# FIANO.net
KiCad netlist of a schematic drawn in EasyEDA Pro
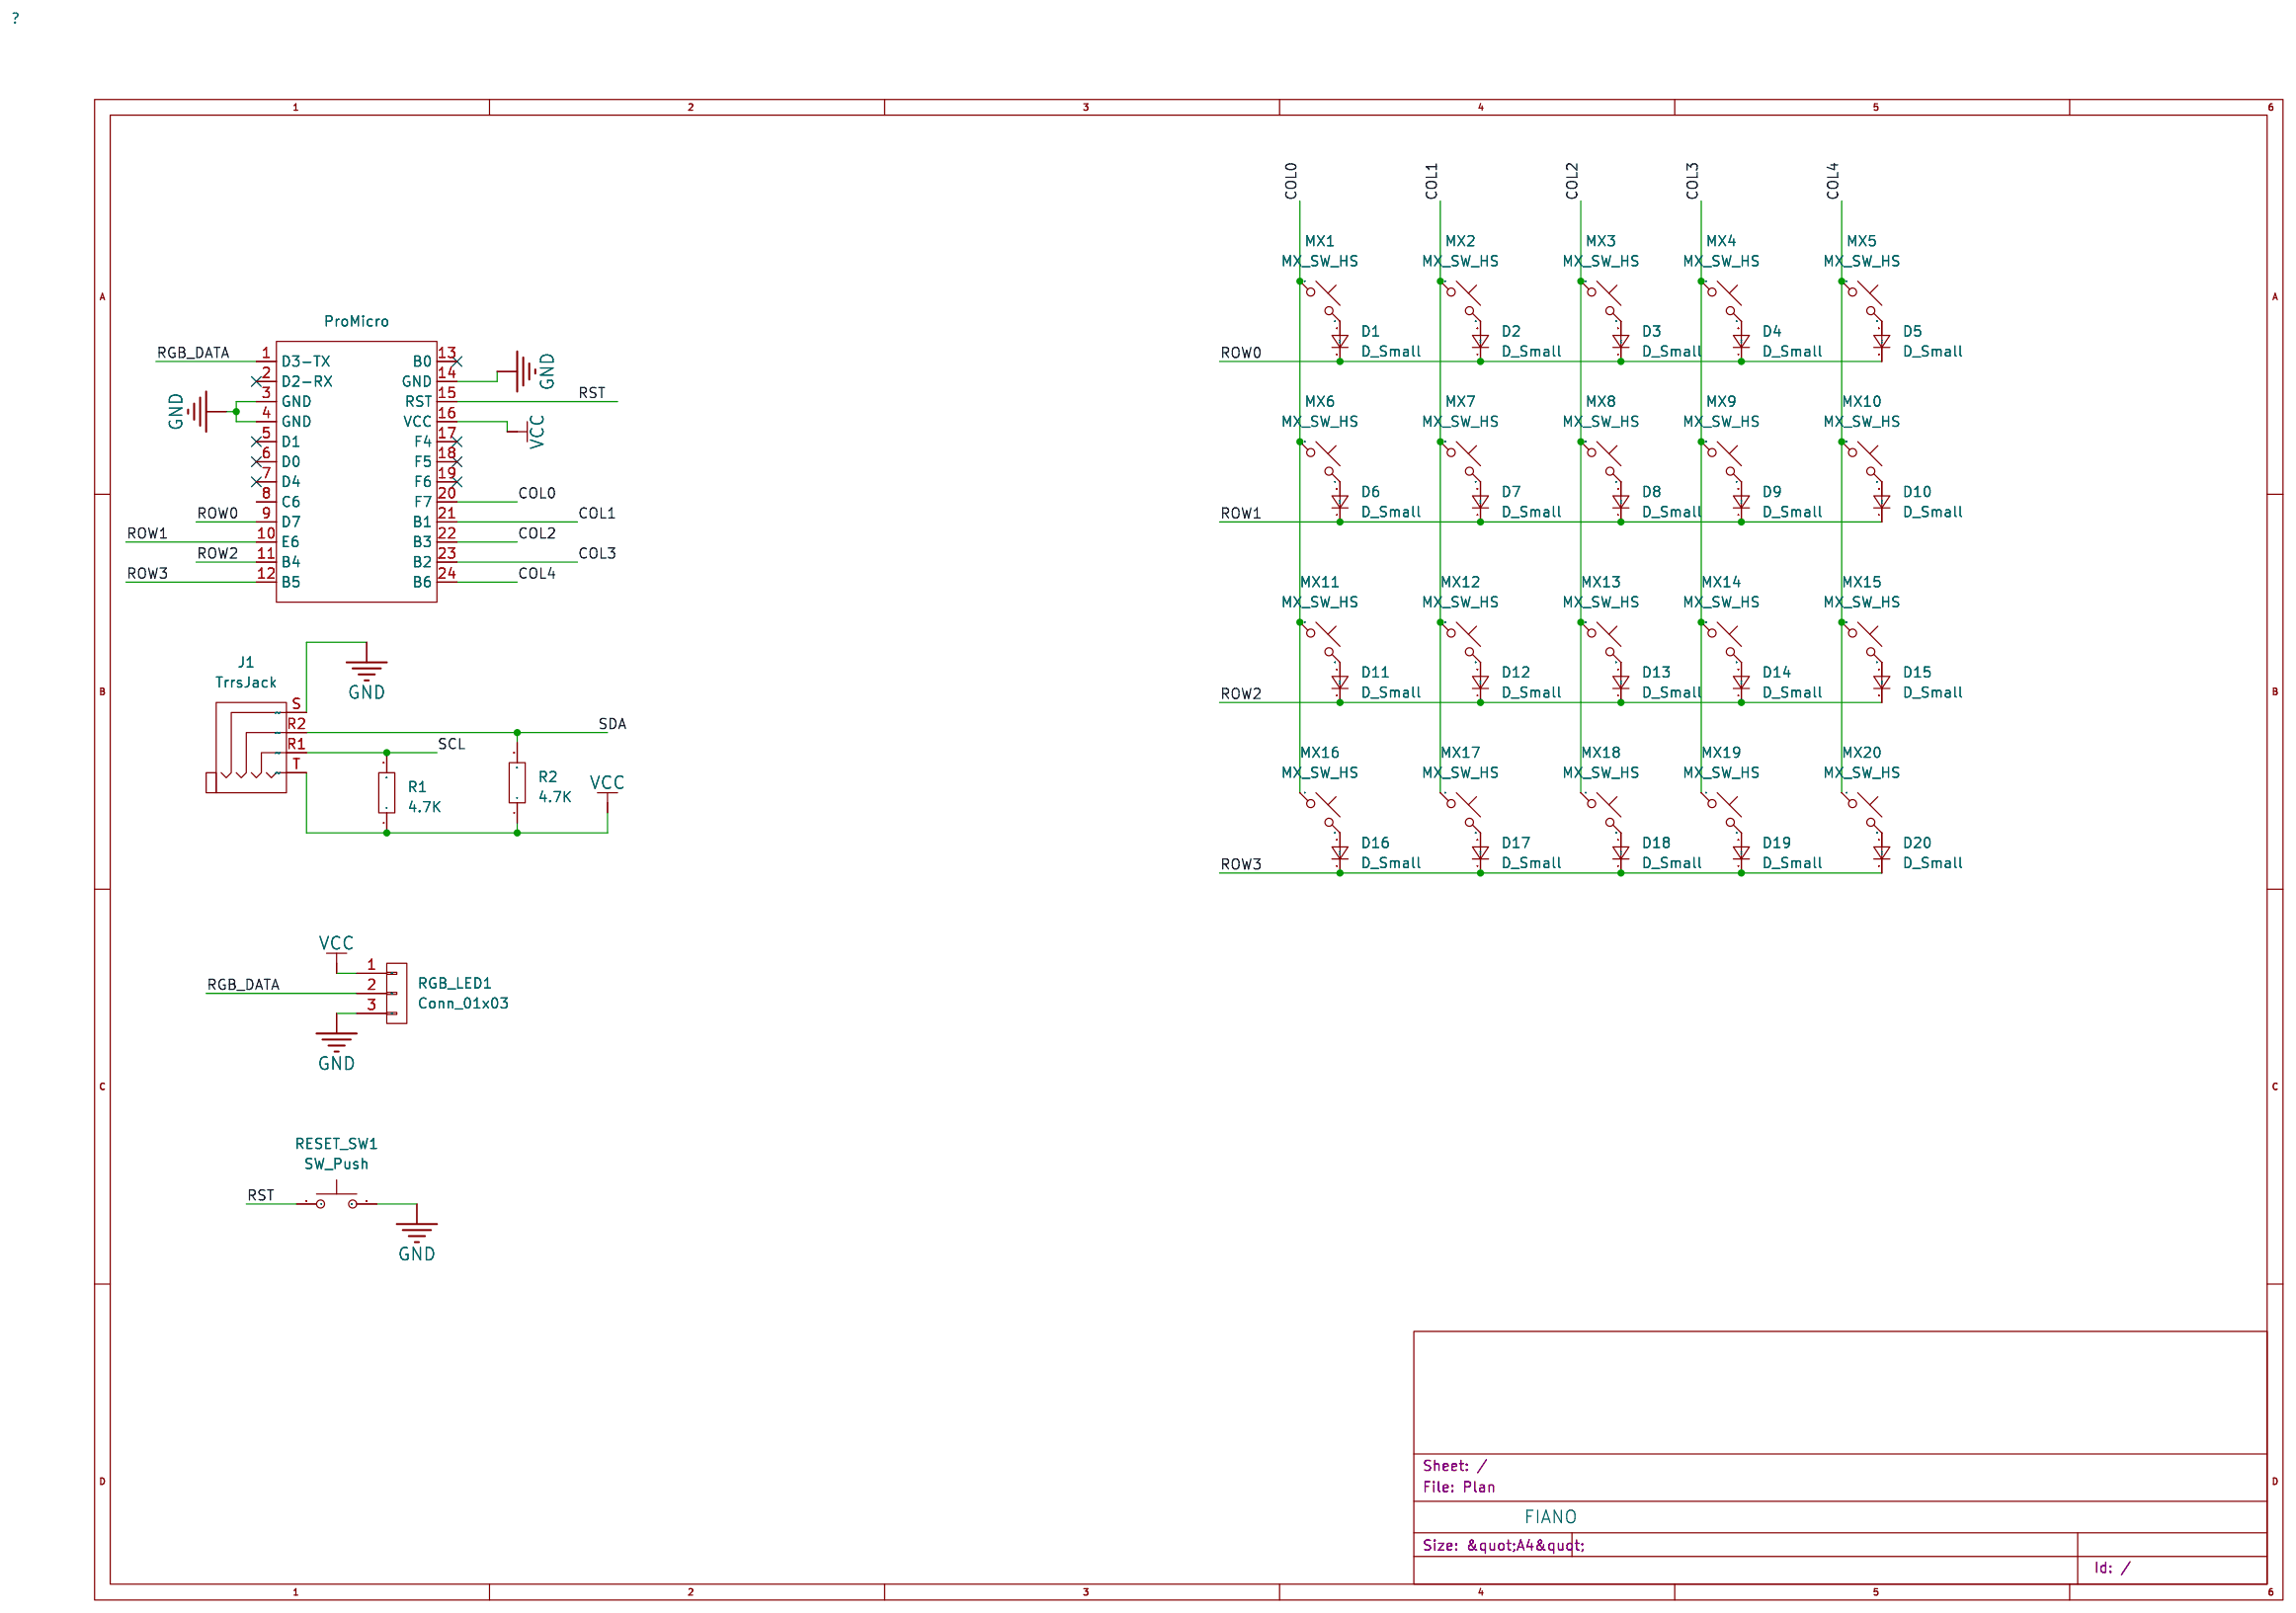
[diagram p0: schematic sheet]

(export (version "E")
  (design (tool "Eeschema 10.0.6"))
  (components
    (comp (ref "D1")
      (value "D_Small")
      (footprint "easyedapro:Keebio-Parts.pretty-master:Diode-hybrid-3pad")
      (description "Diode, small symbol")
      (libsource (lib "easyedapro") (part "Device_D_Small"))
    )
    (comp (ref "D2")
      (value "D_Small")
      (footprint "easyedapro:Keebio-Parts.pretty-master:Diode-hybrid-3pad")
      (description "Diode, small symbol")
      (libsource (lib "easyedapro") (part "Device_D_Small"))
    )
    (comp (ref "D3")
      (value "D_Small")
      (footprint "easyedapro:Keebio-Parts.pretty-master:Diode-hybrid-3pad")
      (description "Diode, small symbol")
      (libsource (lib "easyedapro") (part "Device_D_Small"))
    )
    (comp (ref "D4")
      (value "D_Small")
      (footprint "easyedapro:Keebio-Parts.pretty-master:Diode-hybrid-3pad")
      (description "Diode, small symbol")
      (libsource (lib "easyedapro") (part "Device_D_Small"))
    )
    (comp (ref "D5")
      (value "D_Small")
      (footprint "easyedapro:Keebio-Parts.pretty-master:Diode-hybrid-3pad")
      (description "Diode, small symbol")
      (libsource (lib "easyedapro") (part "Device_D_Small"))
    )
    (comp (ref "D6")
      (value "D_Small")
      (footprint "easyedapro:Keebio-Parts.pretty-master:Diode-hybrid-3pad")
      (description "Diode, small symbol")
      (libsource (lib "easyedapro") (part "Device_D_Small"))
    )
    (comp (ref "D7")
      (value "D_Small")
      (footprint "easyedapro:Keebio-Parts.pretty-master:Diode-hybrid-3pad")
      (description "Diode, small symbol")
      (libsource (lib "easyedapro") (part "Device_D_Small"))
    )
    (comp (ref "D8")
      (value "D_Small")
      (footprint "easyedapro:Keebio-Parts.pretty-master:Diode-hybrid-3pad")
      (description "Diode, small symbol")
      (libsource (lib "easyedapro") (part "Device_D_Small"))
    )
    (comp (ref "D9")
      (value "D_Small")
      (footprint "easyedapro:Keebio-Parts.pretty-master:Diode-hybrid-3pad")
      (description "Diode, small symbol")
      (libsource (lib "easyedapro") (part "Device_D_Small"))
    )
    (comp (ref "D10")
      (value "D_Small")
      (footprint "easyedapro:Keebio-Parts.pretty-master:Diode-hybrid-3pad")
      (description "Diode, small symbol")
      (libsource (lib "easyedapro") (part "Device_D_Small"))
    )
    (comp (ref "D11")
      (value "D_Small")
      (footprint "easyedapro:Keebio-Parts.pretty-master:Diode-hybrid-3pad")
      (description "Diode, small symbol")
      (libsource (lib "easyedapro") (part "Device_D_Small"))
    )
    (comp (ref "D12")
      (value "D_Small")
      (footprint "easyedapro:Keebio-Parts.pretty-master:Diode-hybrid-3pad")
      (description "Diode, small symbol")
      (libsource (lib "easyedapro") (part "Device_D_Small"))
    )
    (comp (ref "D13")
      (value "D_Small")
      (footprint "easyedapro:Keebio-Parts.pretty-master:Diode-hybrid-3pad")
      (description "Diode, small symbol")
      (libsource (lib "easyedapro") (part "Device_D_Small"))
    )
    (comp (ref "D14")
      (value "D_Small")
      (footprint "easyedapro:Keebio-Parts.pretty-master:Diode-hybrid-3pad")
      (description "Diode, small symbol")
      (libsource (lib "easyedapro") (part "Device_D_Small"))
    )
    (comp (ref "D15")
      (value "D_Small")
      (footprint "easyedapro:Keebio-Parts.pretty-master:Diode-hybrid-3pad")
      (description "Diode, small symbol")
      (libsource (lib "easyedapro") (part "Device_D_Small"))
    )
    (comp (ref "D16")
      (value "D_Small")
      (footprint "easyedapro:Keebio-Parts.pretty-master:Diode-hybrid-3pad")
      (description "Diode, small symbol")
      (libsource (lib "easyedapro") (part "Device_D_Small"))
    )
    (comp (ref "D17")
      (value "D_Small")
      (footprint "easyedapro:Keebio-Parts.pretty-master:Diode-hybrid-3pad")
      (description "Diode, small symbol")
      (libsource (lib "easyedapro") (part "Device_D_Small"))
    )
    (comp (ref "D18")
      (value "D_Small")
      (footprint "easyedapro:Keebio-Parts.pretty-master:Diode-hybrid-3pad")
      (description "Diode, small symbol")
      (libsource (lib "easyedapro") (part "Device_D_Small"))
    )
    (comp (ref "D19")
      (value "D_Small")
      (footprint "easyedapro:Keebio-Parts.pretty-master:Diode-hybrid-3pad")
      (description "Diode, small symbol")
      (libsource (lib "easyedapro") (part "Device_D_Small"))
    )
    (comp (ref "D20")
      (value "D_Small")
      (footprint "easyedapro:Keebio-Parts.pretty-master:Diode-hybrid-3pad")
      (description "Diode, small symbol")
      (libsource (lib "easyedapro") (part "Device_D_Small"))
    )
    (comp (ref "J1")
      (value "TrrsJack")
      (footprint "easyedapro:PCM_marbastlib-xp-various:CON_MJ-4PP-9")
      (description "Audio Jack, 4 Poles (TRRS)")
      (libsource (lib "easyedapro") (part "Connector_Audio_AudioJack4"))
    )
    (comp (ref "MX1")
      (value "MX_SW_HS")
      (footprint "easyedapro:PCM_marbastlib-mx:SW_MX_1u")
      (libsource (lib "easyedapro") (part "PCM_marbastlib-mx_MX_SW_HS_CPG151101S11"))
    )
    (comp (ref "MX2")
      (value "MX_SW_HS")
      (footprint "easyedapro:PCM_marbastlib-mx:SW_MX_1u")
      (libsource (lib "easyedapro") (part "PCM_marbastlib-mx_MX_SW_HS_CPG151101S11"))
    )
    (comp (ref "MX3")
      (value "MX_SW_HS")
      (footprint "easyedapro:PCM_marbastlib-mx:SW_MX_1u")
      (libsource (lib "easyedapro") (part "PCM_marbastlib-mx_MX_SW_HS_CPG151101S11"))
    )
    (comp (ref "MX4")
      (value "MX_SW_HS")
      (footprint "easyedapro:PCM_marbastlib-mx:SW_MX_1u")
      (libsource (lib "easyedapro") (part "PCM_marbastlib-mx_MX_SW_HS_CPG151101S11"))
    )
    (comp (ref "MX5")
      (value "MX_SW_HS")
      (footprint "easyedapro:PCM_marbastlib-mx:SW_MX_1u")
      (libsource (lib "easyedapro") (part "PCM_marbastlib-mx_MX_SW_HS_CPG151101S11"))
    )
    (comp (ref "MX6")
      (value "MX_SW_HS")
      (footprint "easyedapro:PCM_marbastlib-mx:SW_MX_1u")
      (libsource (lib "easyedapro") (part "PCM_marbastlib-mx_MX_SW_HS_CPG151101S11"))
    )
    (comp (ref "MX7")
      (value "MX_SW_HS")
      (footprint "easyedapro:PCM_marbastlib-mx:SW_MX_1u")
      (libsource (lib "easyedapro") (part "PCM_marbastlib-mx_MX_SW_HS_CPG151101S11"))
    )
    (comp (ref "MX8")
      (value "MX_SW_HS")
      (footprint "easyedapro:PCM_marbastlib-mx:SW_MX_1u")
      (libsource (lib "easyedapro") (part "PCM_marbastlib-mx_MX_SW_HS_CPG151101S11"))
    )
    (comp (ref "MX9")
      (value "MX_SW_HS")
      (footprint "easyedapro:PCM_marbastlib-mx:SW_MX_1u")
      (libsource (lib "easyedapro") (part "PCM_marbastlib-mx_MX_SW_HS_CPG151101S11"))
    )
    (comp (ref "MX10")
      (value "MX_SW_HS")
      (footprint "easyedapro:PCM_marbastlib-mx:SW_MX_1u")
      (libsource (lib "easyedapro") (part "PCM_marbastlib-mx_MX_SW_HS_CPG151101S11"))
    )
    (comp (ref "MX11")
      (value "MX_SW_HS")
      (footprint "easyedapro:PCM_marbastlib-mx:SW_MX_1u")
      (libsource (lib "easyedapro") (part "PCM_marbastlib-mx_MX_SW_HS_CPG151101S11"))
    )
    (comp (ref "MX12")
      (value "MX_SW_HS")
      (footprint "easyedapro:PCM_marbastlib-mx:SW_MX_1u")
      (libsource (lib "easyedapro") (part "PCM_marbastlib-mx_MX_SW_HS_CPG151101S11"))
    )
    (comp (ref "MX13")
      (value "MX_SW_HS")
      (footprint "easyedapro:PCM_marbastlib-mx:SW_MX_1u")
      (libsource (lib "easyedapro") (part "PCM_marbastlib-mx_MX_SW_HS_CPG151101S11"))
    )
    (comp (ref "MX14")
      (value "MX_SW_HS")
      (footprint "easyedapro:PCM_marbastlib-mx:SW_MX_1u")
      (libsource (lib "easyedapro") (part "PCM_marbastlib-mx_MX_SW_HS_CPG151101S11"))
    )
    (comp (ref "MX15")
      (value "MX_SW_HS")
      (footprint "easyedapro:PCM_marbastlib-mx:SW_MX_1u")
      (libsource (lib "easyedapro") (part "PCM_marbastlib-mx_MX_SW_HS_CPG151101S11"))
    )
    (comp (ref "MX16")
      (value "MX_SW_HS")
      (footprint "easyedapro:PCM_marbastlib-mx:SW_MX_1u")
      (libsource (lib "easyedapro") (part "PCM_marbastlib-mx_MX_SW_HS_CPG151101S11"))
    )
    (comp (ref "MX17")
      (value "MX_SW_HS")
      (footprint "easyedapro:PCM_marbastlib-mx:SW_MX_1u")
      (libsource (lib "easyedapro") (part "PCM_marbastlib-mx_MX_SW_HS_CPG151101S11"))
    )
    (comp (ref "MX18")
      (value "MX_SW_HS")
      (footprint "easyedapro:PCM_marbastlib-mx:SW_MX_1u")
      (libsource (lib "easyedapro") (part "PCM_marbastlib-mx_MX_SW_HS_CPG151101S11"))
    )
    (comp (ref "MX19")
      (value "MX_SW_HS")
      (footprint "easyedapro:PCM_marbastlib-mx:SW_MX_1u")
      (libsource (lib "easyedapro") (part "PCM_marbastlib-mx_MX_SW_HS_CPG151101S11"))
    )
    (comp (ref "MX20")
      (value "MX_SW_HS")
      (footprint "easyedapro:PCM_marbastlib-mx:SW_MX_1u")
      (libsource (lib "easyedapro") (part "PCM_marbastlib-mx_MX_SW_HS_CPG151101S11"))
    )
    (comp (ref "R1")
      (value "4.7K")
      (footprint "easyedapro:R0603")
      (libsource (lib "easyedapro") (part "Res"))
    )
    (comp (ref "R2")
      (value "4.7K")
      (footprint "easyedapro:R0603")
      (libsource (lib "easyedapro") (part "Res"))
    )
    (comp (ref "RESET_SW1")
      (value "SW_Push")
      (description "Push button switch, generic, two pins")
      (libsource (lib "easyedapro") (part "Switch_SW_Push"))
    )
    (comp (ref "RGB_LED1")
      (value "Conn_01x03")
      (libsource (lib "easyedapro") (part "Connector_Generic_Conn_01x03"))
    )
    (comp (ref "U1")
      (value "ProMicro")
      (footprint "easyedapro:PCM_marbastlib-xp-promicroish:ProMicro_USBup")
      (description "Symbol for an Arduino Pro Micro")
      (libsource (lib "easyedapro") (part "PCM_marbastlib-promicroish_Arduino_ProMicro"))
    )
  )
  (nets
    (net (code "1") (name "/COL0") (class "Default")
      (node (ref "MX1") (pin "1") (pinfunction "1_1") (pintype "unspecified"))
      (node (ref "MX11") (pin "1") (pinfunction "1_1") (pintype "unspecified"))
      (node (ref "MX16") (pin "1") (pinfunction "1_1") (pintype "unspecified"))
      (node (ref "MX6") (pin "1") (pinfunction "1_1") (pintype "unspecified"))
      (node (ref "U1") (pin "20") (pinfunction "F7_20") (pintype "bidirectional"))
    )
    (net (code "2") (name "/COL1") (class "Default")
      (node (ref "MX12") (pin "1") (pinfunction "1_1") (pintype "unspecified"))
      (node (ref "MX17") (pin "1") (pinfunction "1_1") (pintype "unspecified"))
      (node (ref "MX2") (pin "1") (pinfunction "1_1") (pintype "unspecified"))
      (node (ref "MX7") (pin "1") (pinfunction "1_1") (pintype "unspecified"))
      (node (ref "U1") (pin "21") (pinfunction "B1_21") (pintype "bidirectional"))
    )
    (net (code "3") (name "/COL2") (class "Default")
      (node (ref "MX13") (pin "1") (pinfunction "1_1") (pintype "unspecified"))
      (node (ref "MX18") (pin "1") (pinfunction "1_1") (pintype "unspecified"))
      (node (ref "MX3") (pin "1") (pinfunction "1_1") (pintype "unspecified"))
      (node (ref "MX8") (pin "1") (pinfunction "1_1") (pintype "unspecified"))
      (node (ref "U1") (pin "22") (pinfunction "B3_22") (pintype "bidirectional"))
    )
    (net (code "4") (name "/COL3") (class "Default")
      (node (ref "MX14") (pin "1") (pinfunction "1_1") (pintype "unspecified"))
      (node (ref "MX19") (pin "1") (pinfunction "1_1") (pintype "unspecified"))
      (node (ref "MX4") (pin "1") (pinfunction "1_1") (pintype "unspecified"))
      (node (ref "MX9") (pin "1") (pinfunction "1_1") (pintype "unspecified"))
      (node (ref "U1") (pin "23") (pinfunction "B2_23") (pintype "bidirectional"))
    )
    (net (code "5") (name "/COL4") (class "Default")
      (node (ref "MX10") (pin "1") (pinfunction "1_1") (pintype "unspecified"))
      (node (ref "MX15") (pin "1") (pinfunction "1_1") (pintype "unspecified"))
      (node (ref "MX20") (pin "1") (pinfunction "1_1") (pintype "unspecified"))
      (node (ref "MX5") (pin "1") (pinfunction "1_1") (pintype "unspecified"))
      (node (ref "U1") (pin "24") (pinfunction "B6_24") (pintype "bidirectional"))
    )
    (net (code "6") (name "/RGB_DATA") (class "Default")
      (node (ref "RGB_LED1") (pin "2") (pinfunction "Pin_2_2") (pintype "unspecified"))
      (node (ref "U1") (pin "1") (pinfunction "D3-TX_1") (pintype "bidirectional"))
    )
    (net (code "7") (name "/ROW0") (class "Default")
      (node (ref "D1") (pin "1") (pinfunction "K_1") (pintype "unspecified"))
      (node (ref "D2") (pin "1") (pinfunction "K_1") (pintype "unspecified"))
      (node (ref "D3") (pin "1") (pinfunction "K_1") (pintype "unspecified"))
      (node (ref "D4") (pin "1") (pinfunction "K_1") (pintype "unspecified"))
      (node (ref "D5") (pin "1") (pinfunction "K_1") (pintype "unspecified"))
      (node (ref "U1") (pin "9") (pinfunction "D7_9") (pintype "bidirectional"))
    )
    (net (code "8") (name "/ROW1") (class "Default")
      (node (ref "D10") (pin "1") (pinfunction "K_1") (pintype "unspecified"))
      (node (ref "D6") (pin "1") (pinfunction "K_1") (pintype "unspecified"))
      (node (ref "D7") (pin "1") (pinfunction "K_1") (pintype "unspecified"))
      (node (ref "D8") (pin "1") (pinfunction "K_1") (pintype "unspecified"))
      (node (ref "D9") (pin "1") (pinfunction "K_1") (pintype "unspecified"))
      (node (ref "U1") (pin "10") (pinfunction "E6_10") (pintype "bidirectional"))
    )
    (net (code "9") (name "/ROW2") (class "Default")
      (node (ref "D11") (pin "1") (pinfunction "K_1") (pintype "unspecified"))
      (node (ref "D12") (pin "1") (pinfunction "K_1") (pintype "unspecified"))
      (node (ref "D13") (pin "1") (pinfunction "K_1") (pintype "unspecified"))
      (node (ref "D14") (pin "1") (pinfunction "K_1") (pintype "unspecified"))
      (node (ref "D15") (pin "1") (pinfunction "K_1") (pintype "unspecified"))
      (node (ref "U1") (pin "11") (pinfunction "B4_11") (pintype "bidirectional"))
    )
    (net (code "10") (name "/ROW3") (class "Default")
      (node (ref "D16") (pin "1") (pinfunction "K_1") (pintype "unspecified"))
      (node (ref "D17") (pin "1") (pinfunction "K_1") (pintype "unspecified"))
      (node (ref "D18") (pin "1") (pinfunction "K_1") (pintype "unspecified"))
      (node (ref "D19") (pin "1") (pinfunction "K_1") (pintype "unspecified"))
      (node (ref "D20") (pin "1") (pinfunction "K_1") (pintype "unspecified"))
      (node (ref "U1") (pin "12") (pinfunction "B5_12") (pintype "bidirectional"))
    )
    (net (code "11") (name "/RST") (class "Default")
      (node (ref "RESET_SW1") (pin "1") (pinfunction "1_1") (pintype "unspecified"))
      (node (ref "U1") (pin "15") (pinfunction "RST_15") (pintype "bidirectional"))
    )
    (net (code "12") (name "/SCL") (class "Default")
      (node (ref "J1") (pin "R1") (pinfunction "~_R1") (pintype "unspecified"))
      (node (ref "R1") (pin "2") (pinfunction "2_2") (pintype "input"))
    )
    (net (code "13") (name "/SDA") (class "Default")
      (node (ref "J1") (pin "R2") (pinfunction "~_R2") (pintype "unspecified"))
      (node (ref "R2") (pin "2") (pinfunction "2_2") (pintype "input"))
    )
    (net (code "14") (name "GND") (class "Default")
      (node (ref "J1") (pin "S") (pinfunction "~_S") (pintype "unspecified"))
      (node (ref "RESET_SW1") (pin "2") (pinfunction "2_2") (pintype "unspecified"))
      (node (ref "RGB_LED1") (pin "3") (pinfunction "Pin_3_3") (pintype "unspecified"))
      (node (ref "U1") (pin "14") (pinfunction "GND_14") (pintype "unspecified"))
      (node (ref "U1") (pin "3") (pinfunction "GND_3") (pintype "unspecified"))
      (node (ref "U1") (pin "4") (pinfunction "GND_4") (pintype "unspecified"))
    )
    (net (code "15") (name "Net-(D1-A)") (class "Default")
      (node (ref "D1") (pin "2") (pinfunction "A_2") (pintype "unspecified"))
      (node (ref "MX1") (pin "2") (pinfunction "2_2") (pintype "unspecified"))
    )
    (net (code "16") (name "Net-(D2-A)") (class "Default")
      (node (ref "D2") (pin "2") (pinfunction "A_2") (pintype "unspecified"))
      (node (ref "MX2") (pin "2") (pinfunction "2_2") (pintype "unspecified"))
    )
    (net (code "17") (name "Net-(D3-A)") (class "Default")
      (node (ref "D3") (pin "2") (pinfunction "A_2") (pintype "unspecified"))
      (node (ref "MX3") (pin "2") (pinfunction "2_2") (pintype "unspecified"))
    )
    (net (code "18") (name "Net-(D4-A)") (class "Default")
      (node (ref "D4") (pin "2") (pinfunction "A_2") (pintype "unspecified"))
      (node (ref "MX4") (pin "2") (pinfunction "2_2") (pintype "unspecified"))
    )
    (net (code "19") (name "Net-(D5-A)") (class "Default")
      (node (ref "D5") (pin "2") (pinfunction "A_2") (pintype "unspecified"))
      (node (ref "MX5") (pin "2") (pinfunction "2_2") (pintype "unspecified"))
    )
    (net (code "20") (name "Net-(D6-A)") (class "Default")
      (node (ref "D6") (pin "2") (pinfunction "A_2") (pintype "unspecified"))
      (node (ref "MX6") (pin "2") (pinfunction "2_2") (pintype "unspecified"))
    )
    (net (code "21") (name "Net-(D7-A)") (class "Default")
      (node (ref "D7") (pin "2") (pinfunction "A_2") (pintype "unspecified"))
      (node (ref "MX7") (pin "2") (pinfunction "2_2") (pintype "unspecified"))
    )
    (net (code "22") (name "Net-(D8-A)") (class "Default")
      (node (ref "D8") (pin "2") (pinfunction "A_2") (pintype "unspecified"))
      (node (ref "MX8") (pin "2") (pinfunction "2_2") (pintype "unspecified"))
    )
    (net (code "23") (name "Net-(D9-A)") (class "Default")
      (node (ref "D9") (pin "2") (pinfunction "A_2") (pintype "unspecified"))
      (node (ref "MX9") (pin "2") (pinfunction "2_2") (pintype "unspecified"))
    )
    (net (code "24") (name "Net-(D10-A)") (class "Default")
      (node (ref "D10") (pin "2") (pinfunction "A_2") (pintype "unspecified"))
      (node (ref "MX10") (pin "2") (pinfunction "2_2") (pintype "unspecified"))
    )
    (net (code "25") (name "Net-(D11-A)") (class "Default")
      (node (ref "D11") (pin "2") (pinfunction "A_2") (pintype "unspecified"))
      (node (ref "MX11") (pin "2") (pinfunction "2_2") (pintype "unspecified"))
    )
    (net (code "26") (name "Net-(D12-A)") (class "Default")
      (node (ref "D12") (pin "2") (pinfunction "A_2") (pintype "unspecified"))
      (node (ref "MX12") (pin "2") (pinfunction "2_2") (pintype "unspecified"))
    )
    (net (code "27") (name "Net-(D13-A)") (class "Default")
      (node (ref "D13") (pin "2") (pinfunction "A_2") (pintype "unspecified"))
      (node (ref "MX13") (pin "2") (pinfunction "2_2") (pintype "unspecified"))
    )
    (net (code "28") (name "Net-(D14-A)") (class "Default")
      (node (ref "D14") (pin "2") (pinfunction "A_2") (pintype "unspecified"))
      (node (ref "MX14") (pin "2") (pinfunction "2_2") (pintype "unspecified"))
    )
    (net (code "29") (name "Net-(D15-A)") (class "Default")
      (node (ref "D15") (pin "2") (pinfunction "A_2") (pintype "unspecified"))
      (node (ref "MX15") (pin "2") (pinfunction "2_2") (pintype "unspecified"))
    )
    (net (code "30") (name "Net-(D16-A)") (class "Default")
      (node (ref "D16") (pin "2") (pinfunction "A_2") (pintype "unspecified"))
      (node (ref "MX16") (pin "2") (pinfunction "2_2") (pintype "unspecified"))
    )
    (net (code "31") (name "Net-(D17-A)") (class "Default")
      (node (ref "D17") (pin "2") (pinfunction "A_2") (pintype "unspecified"))
      (node (ref "MX17") (pin "2") (pinfunction "2_2") (pintype "unspecified"))
    )
    (net (code "32") (name "Net-(D18-A)") (class "Default")
      (node (ref "D18") (pin "2") (pinfunction "A_2") (pintype "unspecified"))
      (node (ref "MX18") (pin "2") (pinfunction "2_2") (pintype "unspecified"))
    )
    (net (code "33") (name "Net-(D19-A)") (class "Default")
      (node (ref "D19") (pin "2") (pinfunction "A_2") (pintype "unspecified"))
      (node (ref "MX19") (pin "2") (pinfunction "2_2") (pintype "unspecified"))
    )
    (net (code "34") (name "Net-(D20-A)") (class "Default")
      (node (ref "D20") (pin "2") (pinfunction "A_2") (pintype "unspecified"))
      (node (ref "MX20") (pin "2") (pinfunction "2_2") (pintype "unspecified"))
    )
    (net (code "35") (name "VCC") (class "Default")
      (node (ref "J1") (pin "T") (pinfunction "~_T") (pintype "unspecified"))
      (node (ref "R1") (pin "1") (pinfunction "1_1") (pintype "input"))
      (node (ref "R2") (pin "1") (pinfunction "1_1") (pintype "input"))
      (node (ref "RGB_LED1") (pin "1") (pinfunction "Pin_1_1") (pintype "unspecified"))
      (node (ref "U1") (pin "16") (pinfunction "VCC_16") (pintype "unspecified"))
    )
    (net (code "36") (name "unconnected-(U1-B0-Pad13)") (class "Default")
      (node (ref "U1") (pin "13") (pinfunction "B0_13") (pintype "bidirectional+no_connect"))
    )
    (net (code "37") (name "unconnected-(U1-C6-Pad8)") (class "Default")
      (node (ref "U1") (pin "8") (pinfunction "C6_8") (pintype "bidirectional"))
    )
    (net (code "38") (name "unconnected-(U1-D0-Pad6)") (class "Default")
      (node (ref "U1") (pin "6") (pinfunction "D0_6") (pintype "bidirectional+no_connect"))
    )
    (net (code "39") (name "unconnected-(U1-D1-Pad5)") (class "Default")
      (node (ref "U1") (pin "5") (pinfunction "D1_5") (pintype "bidirectional+no_connect"))
    )
    (net (code "40") (name "unconnected-(U1-D2-RX-Pad2)") (class "Default")
      (node (ref "U1") (pin "2") (pinfunction "D2-RX_2") (pintype "bidirectional+no_connect"))
    )
    (net (code "41") (name "unconnected-(U1-D4-Pad7)") (class "Default")
      (node (ref "U1") (pin "7") (pinfunction "D4_7") (pintype "bidirectional+no_connect"))
    )
    (net (code "42") (name "unconnected-(U1-F4-Pad17)") (class "Default")
      (node (ref "U1") (pin "17") (pinfunction "F4_17") (pintype "bidirectional+no_connect"))
    )
    (net (code "43") (name "unconnected-(U1-F5-Pad18)") (class "Default")
      (node (ref "U1") (pin "18") (pinfunction "F5_18") (pintype "bidirectional+no_connect"))
    )
    (net (code "44") (name "unconnected-(U1-F6-Pad19)") (class "Default")
      (node (ref "U1") (pin "19") (pinfunction "F6_19") (pintype "bidirectional+no_connect"))
    )
  )
)
